# VL53L1X.net
KiCad netlist of a schematic drawn in EAGLE
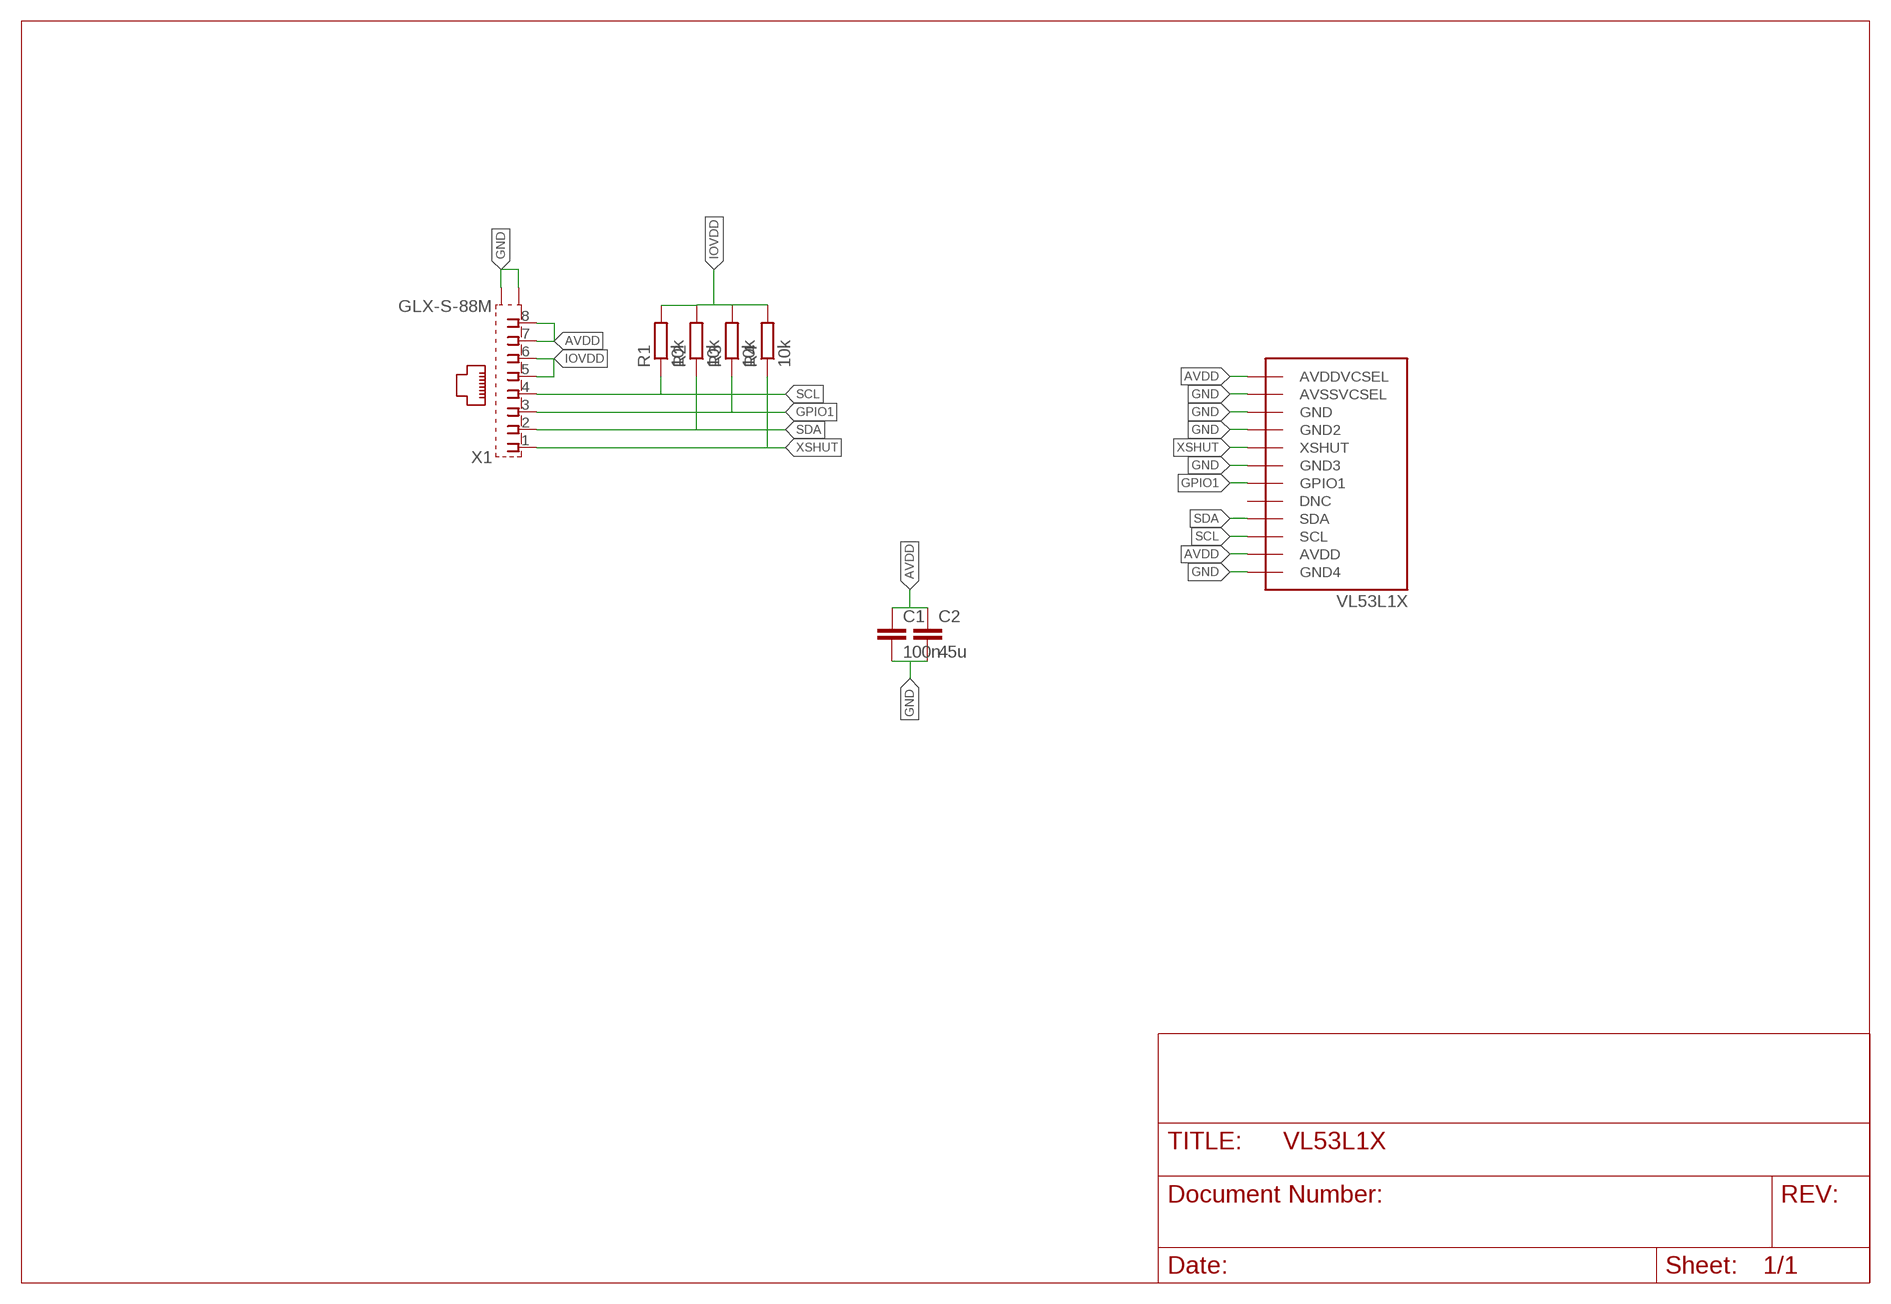
[diagram p0: schematic, sheet 1]

(export (version "E")
  (design (tool "Eeschema 10.0.6"))
  (components
    (comp (ref "C1")
      (value "100n")
      (footprint "eagle-import:C0603")
      (libsource (lib "eagle-import") (part "C-EUC0603"))
    )
    (comp (ref "C2")
      (value "45u")
      (footprint "eagle-import:C0603")
      (libsource (lib "eagle-import") (part "C-EUC0603"))
    )
    (comp (ref "R1")
      (value "10k")
      (footprint "eagle-import:R0603")
      (libsource (lib "eagle-import") (part "R-EU_R0603"))
    )
    (comp (ref "R2")
      (value "10k")
      (footprint "eagle-import:R0603")
      (libsource (lib "eagle-import") (part "R-EU_R0603"))
    )
    (comp (ref "R3")
      (value "10k")
      (footprint "eagle-import:R0603")
      (libsource (lib "eagle-import") (part "R-EU_R0603"))
    )
    (comp (ref "R4")
      (value "10k")
      (footprint "eagle-import:R0603")
      (libsource (lib "eagle-import") (part "R-EU_R0603"))
    )
    (comp (ref "U$1")
      (value "VL53L1X")
      (footprint "eagle-import:VL53L1X")
      (libsource (lib "eagle-import") (part "VL53L1X"))
    )
    (comp (ref "X1")
      (value "GLX-S-88M")
      (footprint "eagle-import:GLX-S-88M")
      (libsource (lib "eagle-import") (part "GLX-S-88M"))
    )
  )
  (nets
    (net (code "1") (name "AVDD") (class "Default")
      (node (ref "C1") (pin "1") (pinfunction "1_1") (pintype "passive"))
      (node (ref "C2") (pin "1") (pinfunction "1_1") (pintype "passive"))
      (node (ref "U$1") (pin "AVDD") (pinfunction "AVDD_AVDD") (pintype "bidirectional"))
      (node (ref "U$1") (pin "AVDDVCSEL") (pinfunction "AVDDVCSEL_AVDDVCSEL") (pintype "bidirectional"))
      (node (ref "X1") (pin "7") (pinfunction "7_7") (pintype "passive"))
      (node (ref "X1") (pin "8") (pinfunction "8_8") (pintype "passive"))
    )
    (net (code "2") (name "GND") (class "Default")
      (node (ref "C1") (pin "2") (pinfunction "2_2") (pintype "passive"))
      (node (ref "C2") (pin "2") (pinfunction "2_2") (pintype "passive"))
      (node (ref "U$1") (pin "AVSSVCSEL") (pinfunction "AVSSVCSEL_AVSSVCSEL") (pintype "bidirectional"))
      (node (ref "U$1") (pin "GND") (pinfunction "GND_GND") (pintype "bidirectional"))
      (node (ref "U$1") (pin "GND2") (pinfunction "GND2_GND2") (pintype "bidirectional"))
      (node (ref "U$1") (pin "GND3") (pinfunction "GND3_GND3") (pintype "bidirectional"))
      (node (ref "U$1") (pin "GND4") (pinfunction "GND4_GND4") (pintype "bidirectional"))
      (node (ref "X1") (pin "S1") (pinfunction "S1_S1") (pintype "passive"))
      (node (ref "X1") (pin "S2") (pinfunction "S2_S2") (pintype "passive"))
    )
    (net (code "3") (name "GPIO1") (class "Default")
      (node (ref "R3") (pin "1") (pinfunction "1_1") (pintype "passive"))
      (node (ref "U$1") (pin "GPIO1") (pinfunction "GPIO1_GPIO1") (pintype "bidirectional"))
      (node (ref "X1") (pin "3") (pinfunction "3_3") (pintype "passive"))
    )
    (net (code "4") (name "IOVDD") (class "Default")
      (node (ref "R1") (pin "2") (pinfunction "2_2") (pintype "passive"))
      (node (ref "R2") (pin "2") (pinfunction "2_2") (pintype "passive"))
      (node (ref "R3") (pin "2") (pinfunction "2_2") (pintype "passive"))
      (node (ref "R4") (pin "2") (pinfunction "2_2") (pintype "passive"))
      (node (ref "X1") (pin "5") (pinfunction "5_5") (pintype "passive"))
      (node (ref "X1") (pin "6") (pinfunction "6_6") (pintype "passive"))
    )
    (net (code "5") (name "SCL") (class "Default")
      (node (ref "R1") (pin "1") (pinfunction "1_1") (pintype "passive"))
      (node (ref "U$1") (pin "SCL") (pinfunction "SCL_SCL") (pintype "bidirectional"))
      (node (ref "X1") (pin "4") (pinfunction "4_4") (pintype "passive"))
    )
    (net (code "6") (name "SDA") (class "Default")
      (node (ref "R2") (pin "1") (pinfunction "1_1") (pintype "passive"))
      (node (ref "U$1") (pin "SDA") (pinfunction "SDA_SDA") (pintype "bidirectional"))
      (node (ref "X1") (pin "2") (pinfunction "2_2") (pintype "passive"))
    )
    (net (code "7") (name "XSHUT") (class "Default")
      (node (ref "R4") (pin "1") (pinfunction "1_1") (pintype "passive"))
      (node (ref "U$1") (pin "XSHUT") (pinfunction "XSHUT_XSHUT") (pintype "bidirectional"))
      (node (ref "X1") (pin "1") (pinfunction "1_1") (pintype "passive"))
    )
    (net (code "8") (name "unconnected-(U$1-PadDNC)") (class "Default")
      (node (ref "U$1") (pin "DNC") (pinfunction "DNC_DNC") (pintype "bidirectional"))
    )
  )
)
